# nadajnik.net
KiCad netlist of a schematic drawn in EAGLE
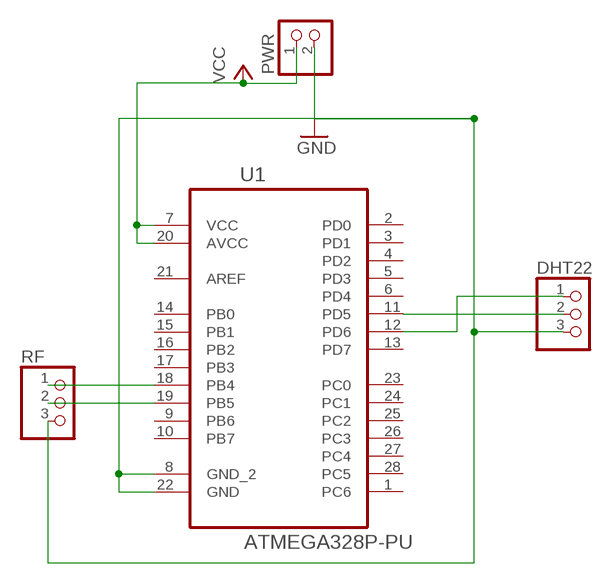
[diagram p0: schematic, sheet 1]

(export (version "E")
  (design (tool "Eeschema 10.0.6"))
  (components
    (comp (ref "DHT22")
      (value "PINHD-1X3")
      (footprint "eagle-import:1X03")
      (libsource (lib "eagle-import") (part "PINHD-1X3"))
    )
    (comp (ref "PWR")
      (value "PINHD-1X2")
      (footprint "eagle-import:1X02")
      (libsource (lib "eagle-import") (part "PINHD-1X2"))
    )
    (comp (ref "RF")
      (value "PINHD-1X3")
      (footprint "eagle-import:1X03")
      (libsource (lib "eagle-import") (part "PINHD-1X3"))
    )
    (comp (ref "U1")
      (value "ATMEGA328P-PU")
      (footprint "eagle-import:DIP254P762X457-28")
      (libsource (lib "eagle-import") (part "ATMEGA328P-PU"))
    )
  )
  (nets
    (net (code "1") (name "GND") (class "Default")
      (node (ref "DHT22") (pin "3") (pinfunction "3_3") (pintype "passive"))
      (node (ref "PWR") (pin "2") (pinfunction "2_2") (pintype "passive"))
      (node (ref "RF") (pin "3") (pinfunction "3_3") (pintype "passive"))
      (node (ref "U1") (pin "22") (pinfunction "GND_22") (pintype "passive"))
      (node (ref "U1") (pin "8") (pinfunction "GND_2_8") (pintype "passive"))
    )
    (net (code "2") (name "Net-(U1-PB4)") (class "Default")
      (node (ref "RF") (pin "1") (pinfunction "1_1") (pintype "passive"))
      (node (ref "U1") (pin "18") (pinfunction "PB4_18") (pintype "bidirectional"))
    )
    (net (code "3") (name "Net-(U1-PB5)") (class "Default")
      (node (ref "RF") (pin "2") (pinfunction "2_2") (pintype "passive"))
      (node (ref "U1") (pin "19") (pinfunction "PB5_19") (pintype "bidirectional"))
    )
    (net (code "4") (name "Net-(U1-PD5)") (class "Default")
      (node (ref "DHT22") (pin "2") (pinfunction "2_2") (pintype "passive"))
      (node (ref "U1") (pin "11") (pinfunction "PD5_11") (pintype "bidirectional"))
    )
    (net (code "5") (name "Net-(U1-PD6)") (class "Default")
      (node (ref "DHT22") (pin "1") (pinfunction "1_1") (pintype "passive"))
      (node (ref "U1") (pin "12") (pinfunction "PD6_12") (pintype "bidirectional"))
    )
    (net (code "6") (name "VCC") (class "Default")
      (node (ref "PWR") (pin "1") (pinfunction "1_1") (pintype "passive"))
      (node (ref "U1") (pin "20") (pinfunction "AVCC_20") (pintype "power_in"))
      (node (ref "U1") (pin "7") (pinfunction "VCC_7") (pintype "power_in"))
    )
    (net (code "7") (name "unconnected-(U1-AREF-Pad21)") (class "Default")
      (node (ref "U1") (pin "21") (pinfunction "AREF_21") (pintype "input"))
    )
    (net (code "8") (name "unconnected-(U1-PB0-Pad14)") (class "Default")
      (node (ref "U1") (pin "14") (pinfunction "PB0_14") (pintype "bidirectional"))
    )
    (net (code "9") (name "unconnected-(U1-PB1-Pad15)") (class "Default")
      (node (ref "U1") (pin "15") (pinfunction "PB1_15") (pintype "bidirectional"))
    )
    (net (code "10") (name "unconnected-(U1-PB2-Pad16)") (class "Default")
      (node (ref "U1") (pin "16") (pinfunction "PB2_16") (pintype "bidirectional"))
    )
    (net (code "11") (name "unconnected-(U1-PB3-Pad17)") (class "Default")
      (node (ref "U1") (pin "17") (pinfunction "PB3_17") (pintype "bidirectional"))
    )
    (net (code "12") (name "unconnected-(U1-PB6-Pad9)") (class "Default")
      (node (ref "U1") (pin "9") (pinfunction "PB6_9") (pintype "bidirectional"))
    )
    (net (code "13") (name "unconnected-(U1-PB7-Pad10)") (class "Default")
      (node (ref "U1") (pin "10") (pinfunction "PB7_10") (pintype "bidirectional"))
    )
    (net (code "14") (name "unconnected-(U1-PC0-Pad23)") (class "Default")
      (node (ref "U1") (pin "23") (pinfunction "PC0_23") (pintype "bidirectional"))
    )
    (net (code "15") (name "unconnected-(U1-PC1-Pad24)") (class "Default")
      (node (ref "U1") (pin "24") (pinfunction "PC1_24") (pintype "bidirectional"))
    )
    (net (code "16") (name "unconnected-(U1-PC2-Pad25)") (class "Default")
      (node (ref "U1") (pin "25") (pinfunction "PC2_25") (pintype "bidirectional"))
    )
    (net (code "17") (name "unconnected-(U1-PC3-Pad26)") (class "Default")
      (node (ref "U1") (pin "26") (pinfunction "PC3_26") (pintype "bidirectional"))
    )
    (net (code "18") (name "unconnected-(U1-PC4-Pad27)") (class "Default")
      (node (ref "U1") (pin "27") (pinfunction "PC4_27") (pintype "bidirectional"))
    )
    (net (code "19") (name "unconnected-(U1-PC5-Pad28)") (class "Default")
      (node (ref "U1") (pin "28") (pinfunction "PC5_28") (pintype "bidirectional"))
    )
    (net (code "20") (name "unconnected-(U1-PC6-Pad1)") (class "Default")
      (node (ref "U1") (pin "1") (pinfunction "PC6_1") (pintype "bidirectional"))
    )
    (net (code "21") (name "unconnected-(U1-PD0-Pad2)") (class "Default")
      (node (ref "U1") (pin "2") (pinfunction "PD0_2") (pintype "bidirectional"))
    )
    (net (code "22") (name "unconnected-(U1-PD1-Pad3)") (class "Default")
      (node (ref "U1") (pin "3") (pinfunction "PD1_3") (pintype "bidirectional"))
    )
    (net (code "23") (name "unconnected-(U1-PD2-Pad4)") (class "Default")
      (node (ref "U1") (pin "4") (pinfunction "PD2_4") (pintype "bidirectional"))
    )
    (net (code "24") (name "unconnected-(U1-PD3-Pad5)") (class "Default")
      (node (ref "U1") (pin "5") (pinfunction "PD3_5") (pintype "bidirectional"))
    )
    (net (code "25") (name "unconnected-(U1-PD4-Pad6)") (class "Default")
      (node (ref "U1") (pin "6") (pinfunction "PD4_6") (pintype "bidirectional"))
    )
    (net (code "26") (name "unconnected-(U1-PD7-Pad13)") (class "Default")
      (node (ref "U1") (pin "13") (pinfunction "PD7_13") (pintype "bidirectional"))
    )
  )
)
